# source_test_datasheet.net
KiCad netlist of a schematic drawn in Altium Designer
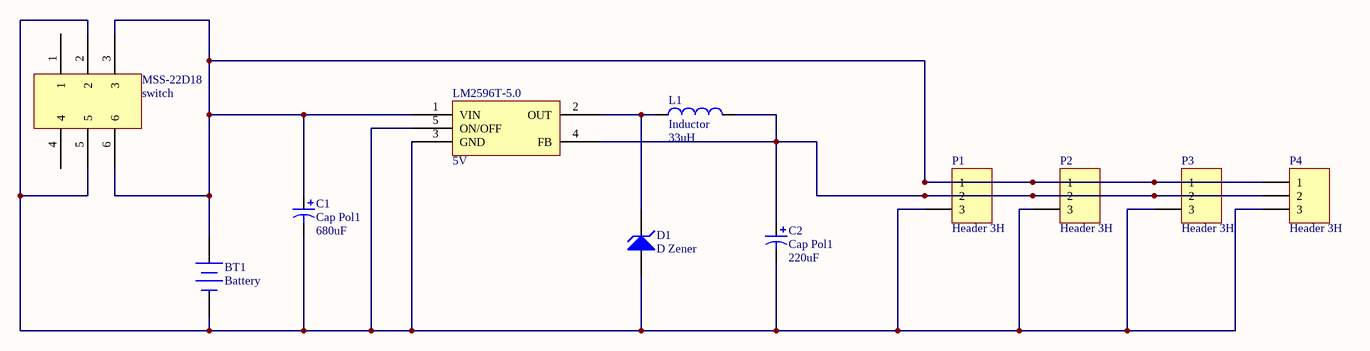
[diagram p0: source_test(datasheet).SchDoc]

(export (version "E")
  (design (tool "Eeschema 10.0.6"))
  (components
    (comp (ref "BT1")
      (value "Battery")
      (footprint "BAT-2")
      (description "Multicell Battery")
      (fields (field (name "PUBLISHER") "Altium Limited"))
      (libsource (lib "Miscellaneous Devices") (part "Battery"))
    )
    (comp (ref "C1")
      (value "Cap Pol1")
      (footprint "RB7.6-15")
      (description "Polarized Capacitor (Radial)")
      (fields (field (name "ALTIUM_VALUE") "680uF") (field (name "PUBLISHER") "Altium Limited"))
      (libsource (lib "Miscellaneous Devices") (part "Cap Pol1"))
    )
    (comp (ref "C2")
      (value "Cap Pol1")
      (footprint "RB7.6-15")
      (description "Polarized Capacitor (Radial)")
      (fields (field (name "ALTIUM_VALUE") "220uF") (field (name "PUBLISHER") "Altium Limited"))
      (libsource (lib "Miscellaneous Devices") (part "Cap Pol1"))
    )
    (comp (ref "D1")
      (value "D Zener")
      (footprint "DIODE-0.7")
      (description "Zener Diode")
      (fields (field (name "PUBLISHER") "Altium Limited"))
      (libsource (lib "Miscellaneous Devices") (part "D Zener"))
    )
    (comp (ref "L1")
      (value "Inductor")
      (footprint "0402-A")
      (fields (field (name "ALTIUM_VALUE") "33uH") (field (name "PUBLISHER") "Altium Limited"))
      (libsource (lib "Miscellaneous Devices") (part "Inductor"))
    )
    (comp (ref "LM2596T-5.0")
      (value "5V")
      (footprint "LM2596T-5.0")
      (libsource (lib "my_Library") (part "LM2596T-5.0"))
    )
    (comp (ref "MSS-22D18")
      (value "switch")
      (footprint "MSS-22D18")
      (libsource (lib "my_Library") (part "MSS-22D18"))
    )
    (comp (ref "P1")
      (value "Header 3H")
      (footprint "HDR1X3H")
      (description "Header, 3-Pin, Right Angle")
      (fields (field (name "PUBLISHER") "Altium Limited"))
      (libsource (lib "Miscellaneous Connectors") (part "Header 3H"))
    )
    (comp (ref "P2")
      (value "Header 3H")
      (footprint "HDR1X3H")
      (description "Header, 3-Pin, Right Angle")
      (fields (field (name "PUBLISHER") "Altium Limited"))
      (libsource (lib "Miscellaneous Connectors") (part "Header 3H"))
    )
    (comp (ref "P3")
      (value "Header 3H")
      (footprint "HDR1X3H")
      (description "Header, 3-Pin, Right Angle")
      (fields (field (name "PUBLISHER") "Altium Limited"))
      (libsource (lib "Miscellaneous Connectors") (part "Header 3H"))
    )
    (comp (ref "P4")
      (value "Header 3H")
      (footprint "HDR1X3H")
      (description "Header, 3-Pin, Right Angle")
      (fields (field (name "PUBLISHER") "Altium Limited"))
      (libsource (lib "Miscellaneous Connectors") (part "Header 3H"))
    )
  )
  (nets
    (net (code "1") (name "Net-(BT1-+)") (class "Default")
      (node (ref "BT1") (pin "1") (pinfunction "+_1") (pintype "passive"))
      (node (ref "C1") (pin "1") (pinfunction "1_1") (pintype "passive"))
      (node (ref "LM2596T-5.0") (pin "1") (pinfunction "VIN_1") (pintype "passive"))
      (node (ref "MSS-22D18") (pin "3") (pinfunction "3_3") (pintype "passive"))
      (node (ref "MSS-22D18") (pin "6") (pinfunction "6_6") (pintype "passive"))
      (node (ref "P1") (pin "1") (pinfunction "1_1") (pintype "passive"))
      (node (ref "P2") (pin "1") (pinfunction "1_1") (pintype "passive"))
      (node (ref "P3") (pin "1") (pinfunction "1_1") (pintype "passive"))
      (node (ref "P4") (pin "1") (pinfunction "1_1") (pintype "passive"))
    )
    (net (code "2") (name "Net-(BT1--)") (class "Default")
      (node (ref "BT1") (pin "2") (pinfunction "-_2") (pintype "passive"))
      (node (ref "C1") (pin "2") (pinfunction "2_2") (pintype "passive"))
      (node (ref "C2") (pin "2") (pinfunction "2_2") (pintype "passive"))
      (node (ref "D1") (pin "1") (pinfunction "A_1") (pintype "passive"))
      (node (ref "LM2596T-5.0") (pin "3") (pinfunction "GND_3") (pintype "passive"))
      (node (ref "LM2596T-5.0") (pin "5") (pinfunction "ON/OFF_5") (pintype "passive"))
      (node (ref "MSS-22D18") (pin "2") (pinfunction "2_2") (pintype "passive"))
      (node (ref "MSS-22D18") (pin "5") (pinfunction "5_5") (pintype "passive"))
      (node (ref "P1") (pin "3") (pinfunction "3_3") (pintype "passive"))
      (node (ref "P2") (pin "3") (pinfunction "3_3") (pintype "passive"))
      (node (ref "P3") (pin "3") (pinfunction "3_3") (pintype "passive"))
      (node (ref "P4") (pin "3") (pinfunction "3_3") (pintype "passive"))
    )
    (net (code "3") (name "Net-(D1-K)") (class "Default")
      (node (ref "D1") (pin "2") (pinfunction "K_2") (pintype "passive"))
      (node (ref "L1") (pin "1") (pinfunction "1_1") (pintype "passive"))
      (node (ref "LM2596T-5.0") (pin "2") (pinfunction "OUT_2") (pintype "passive"))
    )
    (net (code "4") (name "Net-(LM2596T-5.0-FB)") (class "Default")
      (node (ref "C2") (pin "1") (pinfunction "1_1") (pintype "passive"))
      (node (ref "L1") (pin "2") (pinfunction "2_2") (pintype "passive"))
      (node (ref "LM2596T-5.0") (pin "4") (pinfunction "FB_4") (pintype "passive"))
      (node (ref "P1") (pin "2") (pinfunction "2_2") (pintype "passive"))
      (node (ref "P2") (pin "2") (pinfunction "2_2") (pintype "passive"))
      (node (ref "P3") (pin "2") (pinfunction "2_2") (pintype "passive"))
      (node (ref "P4") (pin "2") (pinfunction "2_2") (pintype "passive"))
    )
    (net (code "5") (name "unconnected-(MSS-22D18-Pad1)") (class "Default")
      (node (ref "MSS-22D18") (pin "1") (pinfunction "1_1") (pintype "passive"))
    )
    (net (code "6") (name "unconnected-(MSS-22D18-Pad4)") (class "Default")
      (node (ref "MSS-22D18") (pin "4") (pinfunction "4_4") (pintype "passive"))
    )
  )
)
